# FTDI.net
KiCad netlist of a schematic drawn in EAGLE
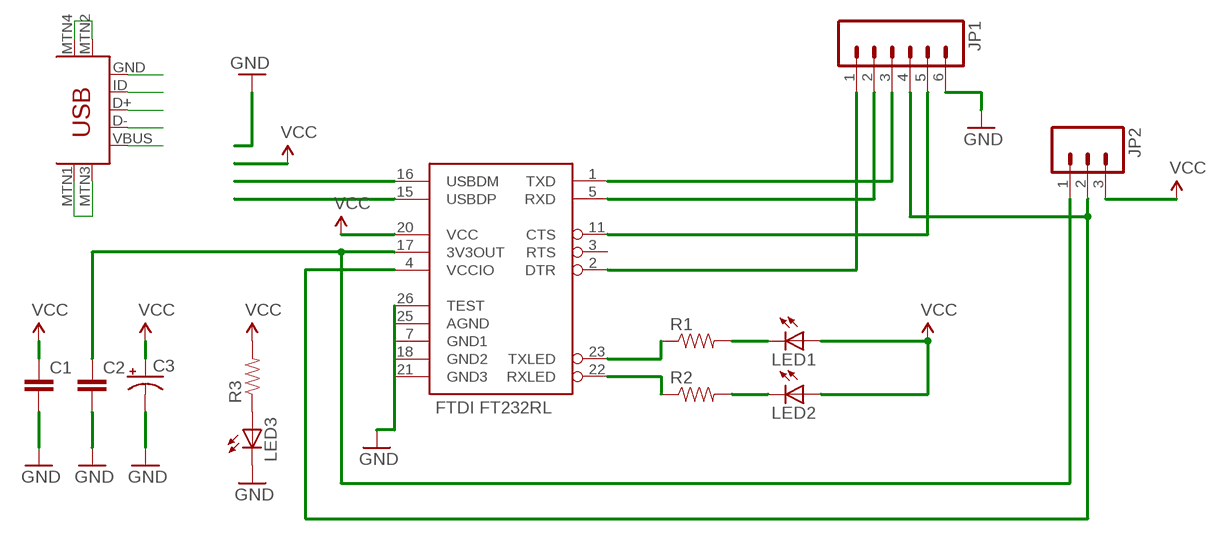
[diagram p0: schematic, sheet 1]

(export (version "E")
  (design (tool "Eeschema 10.0.6"))
  (components
    (comp (ref "C1")
      (value "CAP0603-CAP")
      (footprint "eagle-import:0603-CAP")
      (libsource (lib "eagle-import") (part "CAP0603-CAP"))
    )
    (comp (ref "C2")
      (value "CAP0603-CAP")
      (footprint "eagle-import:0603-CAP")
      (libsource (lib "eagle-import") (part "CAP0603-CAP"))
    )
    (comp (ref "C3")
      (value "CAP_POL1206")
      (footprint "eagle-import:EIA3216")
      (libsource (lib "eagle-import") (part "CAP_POL1206"))
    )
    (comp (ref "JP1")
      (value "M06SIP")
      (footprint "eagle-import:1X06")
      (libsource (lib "eagle-import") (part "M06SIP"))
    )
    (comp (ref "JP2")
      (value "M03PTH")
      (footprint "eagle-import:1X03")
      (libsource (lib "eagle-import") (part "M03PTH"))
    )
    (comp (ref "LED1")
      (value "LED0603")
      (footprint "eagle-import:LED-0603")
      (libsource (lib "eagle-import") (part "LED0603"))
    )
    (comp (ref "LED2")
      (value "LED0603")
      (footprint "eagle-import:LED-0603")
      (libsource (lib "eagle-import") (part "LED0603"))
    )
    (comp (ref "LED3")
      (value "LED0603")
      (footprint "eagle-import:LED-0603")
      (libsource (lib "eagle-import") (part "LED0603"))
    )
    (comp (ref "R1")
      (value "RESISTOR0603-RES")
      (footprint "eagle-import:0603-RES")
      (libsource (lib "eagle-import") (part "RESISTOR0603-RES"))
    )
    (comp (ref "R2")
      (value "RESISTOR0603-RES")
      (footprint "eagle-import:0603-RES")
      (libsource (lib "eagle-import") (part "RESISTOR0603-RES"))
    )
    (comp (ref "R3")
      (value "RESISTOR0603-RES")
      (footprint "eagle-import:0603-RES")
      (libsource (lib "eagle-import") (part "RESISTOR0603-RES"))
    )
    (comp (ref "U$3")
      (value "USB-MINIB-5PIN")
      (footprint "eagle-import:USB-MINIB")
      (libsource (lib "eagle-import") (part "USB-MINIB-5PIN"))
    )
    (comp (ref "U1")
      (value "FT232RL-BASICSSOP")
      (footprint "eagle-import:SSOP28DB")
      (libsource (lib "eagle-import") (part "FT232RL-BASICSSOP"))
    )
  )
  (nets
    (net (code "1") (name "/D+") (class "Default")
      (node (ref "U$3") (pin "D+") (pinfunction "D+_D+") (pintype "bidirectional"))
      (node (ref "U1") (pin "15") (pinfunction "USBDP_15") (pintype "bidirectional"))
    )
    (net (code "2") (name "/D-") (class "Default")
      (node (ref "U$3") (pin "D-") (pinfunction "D-_D-") (pintype "bidirectional"))
      (node (ref "U1") (pin "16") (pinfunction "USBDM_16") (pintype "bidirectional"))
    )
    (net (code "3") (name "GND") (class "Default")
      (node (ref "C1") (pin "2") (pinfunction "2_2") (pintype "passive"))
      (node (ref "C2") (pin "2") (pinfunction "2_2") (pintype "passive"))
      (node (ref "C3") (pin "C") (pinfunction "-_C") (pintype "passive"))
      (node (ref "JP1") (pin "6") (pinfunction "6_6") (pintype "passive"))
      (node (ref "LED3") (pin "C") (pinfunction "C_C") (pintype "passive"))
      (node (ref "U$3") (pin "GND") (pinfunction "GND_GND") (pintype "bidirectional"))
      (node (ref "U$3") (pin "MTN1") (pinfunction "MTN2_MTN1") (pintype "bidirectional"))
      (node (ref "U$3") (pin "MTN2") (pinfunction "MTN3_MTN2") (pintype "bidirectional"))
      (node (ref "U$3") (pin "MTN3") (pinfunction "MTN1_MTN3") (pintype "bidirectional"))
      (node (ref "U$3") (pin "MTN4") (pinfunction "MTN4_MTN4") (pintype "bidirectional"))
      (node (ref "U1") (pin "18") (pinfunction "GND2_18") (pintype "power_in"))
      (node (ref "U1") (pin "21") (pinfunction "GND3_21") (pintype "power_in"))
      (node (ref "U1") (pin "25") (pinfunction "AGND_25") (pintype "power_in"))
      (node (ref "U1") (pin "26") (pinfunction "TEST_26") (pintype "input"))
      (node (ref "U1") (pin "7") (pinfunction "GND1_7") (pintype "power_in"))
    )
    (net (code "4") (name "Net-(LED1-PadC)") (class "Default")
      (node (ref "LED1") (pin "C") (pinfunction "C_C") (pintype "passive"))
      (node (ref "R1") (pin "2") (pinfunction "2_2") (pintype "passive"))
    )
    (net (code "5") (name "Net-(LED2-PadC)") (class "Default")
      (node (ref "LED2") (pin "C") (pinfunction "C_C") (pintype "passive"))
      (node (ref "R2") (pin "2") (pinfunction "2_2") (pintype "passive"))
    )
    (net (code "6") (name "Net-(LED3-PadA)") (class "Default")
      (node (ref "LED3") (pin "A") (pinfunction "A_A") (pintype "passive"))
      (node (ref "R3") (pin "1") (pinfunction "1_1") (pintype "passive"))
    )
    (net (code "7") (name "Net-(U1-3V3OUT)") (class "Default")
      (node (ref "C2") (pin "1") (pinfunction "1_1") (pintype "passive"))
      (node (ref "JP2") (pin "1") (pinfunction "1_1") (pintype "passive"))
      (node (ref "U1") (pin "17") (pinfunction "3V3OUT_17") (pintype "output"))
    )
    (net (code "8") (name "Net-(U1-CTS)") (class "Default")
      (node (ref "JP1") (pin "5") (pinfunction "5_5") (pintype "passive"))
      (node (ref "U1") (pin "11") (pinfunction "CTS_11") (pintype "bidirectional"))
    )
    (net (code "9") (name "Net-(U1-DTR)") (class "Default")
      (node (ref "JP1") (pin "1") (pinfunction "1_1") (pintype "passive"))
      (node (ref "U1") (pin "2") (pinfunction "DTR_2") (pintype "bidirectional"))
    )
    (net (code "10") (name "Net-(U1-RXD)") (class "Default")
      (node (ref "JP1") (pin "2") (pinfunction "2_2") (pintype "passive"))
      (node (ref "U1") (pin "5") (pinfunction "RXD_5") (pintype "input"))
    )
    (net (code "11") (name "Net-(U1-RXLED)") (class "Default")
      (node (ref "R2") (pin "1") (pinfunction "1_1") (pintype "passive"))
      (node (ref "U1") (pin "22") (pinfunction "RXLED_22") (pintype "bidirectional"))
    )
    (net (code "12") (name "Net-(U1-TXD)") (class "Default")
      (node (ref "JP1") (pin "3") (pinfunction "3_3") (pintype "passive"))
      (node (ref "U1") (pin "1") (pinfunction "TXD_1") (pintype "output"))
    )
    (net (code "13") (name "Net-(U1-TXLED)") (class "Default")
      (node (ref "R1") (pin "1") (pinfunction "1_1") (pintype "passive"))
      (node (ref "U1") (pin "23") (pinfunction "TXLED_23") (pintype "bidirectional"))
    )
    (net (code "14") (name "Net-(U1-VCCIO)") (class "Default")
      (node (ref "JP1") (pin "4") (pinfunction "4_4") (pintype "passive"))
      (node (ref "JP2") (pin "2") (pinfunction "2_2") (pintype "passive"))
      (node (ref "U1") (pin "4") (pinfunction "VCCIO_4") (pintype "power_in"))
    )
    (net (code "15") (name "VCC") (class "Default")
      (node (ref "C1") (pin "1") (pinfunction "1_1") (pintype "passive"))
      (node (ref "C3") (pin "A") (pinfunction "+_A") (pintype "passive"))
      (node (ref "JP2") (pin "3") (pinfunction "3_3") (pintype "passive"))
      (node (ref "LED1") (pin "A") (pinfunction "A_A") (pintype "passive"))
      (node (ref "LED2") (pin "A") (pinfunction "A_A") (pintype "passive"))
      (node (ref "R3") (pin "2") (pinfunction "2_2") (pintype "passive"))
      (node (ref "U$3") (pin "VBUS") (pinfunction "VBUS_VBUS") (pintype "bidirectional"))
      (node (ref "U1") (pin "20") (pinfunction "VCC_20") (pintype "power_in"))
    )
    (net (code "16") (name "unconnected-(U$3-PadID)") (class "Default")
      (node (ref "U$3") (pin "ID") (pinfunction "ID_ID") (pintype "bidirectional"))
    )
    (net (code "17") (name "unconnected-(U1-RTS-Pad3)") (class "Default")
      (node (ref "U1") (pin "3") (pinfunction "RTS_3") (pintype "bidirectional"))
    )
  )
)
